# Power.net
KiCad netlist of a schematic drawn in Altium Designer
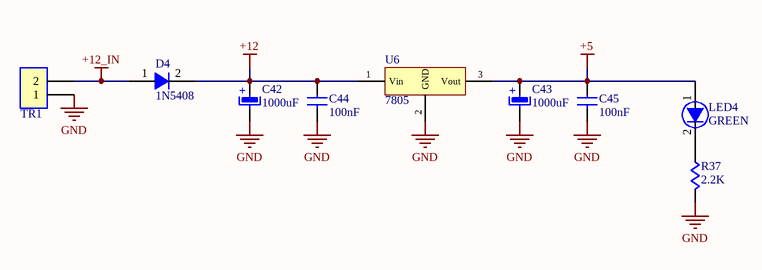
[diagram p0: Power.SchDoc]

(export (version "E")
  (design (tool "Eeschema 10.0.6"))
  (components
    (comp (ref "C42")
      (value "1000uF")
      (footprint "CAP-Elec-10x25-5")
      (description "CAPACITOR")
      (fields
        (field (name "VOLTAGE") "25V")
        (field (name "Comment") "CAP Elec 1000uF-25V-10x25-THD")
        (field (name "PUBLISHER") "Mahdi Bagherzadeh")
      )
      (libsource (lib "Mahdi-Bagherzadeh") (part "CAP-ELEC"))
    )
    (comp (ref "C43")
      (value "1000uF")
      (footprint "CAP-ELEC-SMD-D")
      (description "CAPACITOR")
      (fields
        (field (name "VOLTAGE") "10V")
        (field (name "Comment") "CAP Elec 1000uF-10V-10x25-THD")
        (field (name "PUBLISHER") "Mahdi Bagherzadeh")
      )
      (libsource (lib "Mahdi-Bagherzadeh") (part "CAP-ELEC"))
    )
    (comp (ref "C44")
      (value "100nF")
      (footprint "C-0805")
      (description "CAPACITOR")
      (fields
        (field (name "VOLTAGE") "50V")
        (field (name "TOLERANCE") "X7R")
        (field (name "PUBLISHER") "Mahdi Bagherzadeh")
      )
      (libsource (lib "Mahdi-Bagherzadeh") (part "CAP-CER"))
    )
    (comp (ref "C45")
      (value "100nF")
      (footprint "C-0805")
      (description "CAPACITOR")
      (fields
        (field (name "VOLTAGE") "50V")
        (field (name "TOLERANCE") "X7R")
        (field (name "PUBLISHER") "Mahdi Bagherzadeh")
      )
      (libsource (lib "Mahdi-Bagherzadeh") (part "CAP-CER"))
    )
    (comp (ref "D4")
      (value "Diode 1N5408-SMD")
      (footprint "D-DO214")
      (description "DIODE")
      (fields (field (name "CODE") "1N5408") (field (name "PUBLISHER") "Mahdi Bagherzadeh"))
      (libsource (lib "Mahdi-Bagherzadeh") (part "DIODE"))
    )
    (comp (ref "LED4")
      (value "LED GREEN-1206-SMD")
      (footprint "LED-1206-Y")
      (description "LED")
      (fields (field (name "COLOR") "GREEN") (field (name "PUBLISHER") "Mahdi Bagherzadeh"))
      (libsource (lib "Mahdi-Bagherzadeh") (part "LED"))
    )
    (comp (ref "R37")
      (value "2.2K")
      (footprint "RES-THD-1W-hori-Ls700mil")
      (description "RESISTOR")
      (fields
        (field (name "TOLERANCE") "5%")
        (field (name "POWER") "1/8W")
        (field (name "PUBLISHER") "Mahdi Bagherzadeh")
      )
      (libsource (lib "Mahdi-Bagherzadeh") (part "RES"))
    )
    (comp (ref "TR1")
      (value "Terminal KF?/Phoenix-2Pin-?mm-Straight/Right")
      (footprint "KF129-2pin")
      (description "TERMINAL")
      (fields (field (name "PUBLISHER") "Mahdi Bagherzadeh"))
      (libsource (lib "Mahdi-Bagherzadeh") (part "TEMINAL-2pin"))
    )
    (comp (ref "U6")
      (value "Reg 7805-5V-THD")
      (footprint "TO220-HEARSINK-1")
      (description "REGULATOR")
      (fields
        (field (name "VOLTAGE") "5V")
        (field (name "CODE") "7805")
        (field (name "PUBLISHER") "Mahdi Bagherzadeh")
      )
      (libsource (lib "Mahdi-Bagherzadeh") (part "78Mxx"))
    )
  )
  (nets
    (net (code "1") (name "+5") (class "Default")
      (node (ref "C43") (pin "1") (pinfunction "1_1") (pintype "passive"))
      (node (ref "C45") (pin "1") (pinfunction "1_1") (pintype "passive"))
      (node (ref "LED4") (pin "1") (pinfunction "A_1") (pintype "passive"))
      (node (ref "U6") (pin "3") (pinfunction "Vout_3") (pintype "power_in"))
    )
    (net (code "2") (name "+12") (class "Default")
      (node (ref "C42") (pin "1") (pinfunction "1_1") (pintype "passive"))
      (node (ref "C44") (pin "1") (pinfunction "1_1") (pintype "passive"))
      (node (ref "D4") (pin "2") (pinfunction "C_2") (pintype "passive"))
      (node (ref "U6") (pin "1") (pinfunction "Vin_1") (pintype "power_in"))
    )
    (net (code "3") (name "+12_IN") (class "Default")
      (node (ref "D4") (pin "1") (pinfunction "A_1") (pintype "passive"))
      (node (ref "TR1") (pin "2") (pinfunction "2_2") (pintype "passive"))
    )
    (net (code "4") (name "GND") (class "Default")
      (node (ref "C42") (pin "2") (pinfunction "2_2") (pintype "passive"))
      (node (ref "C43") (pin "2") (pinfunction "2_2") (pintype "passive"))
      (node (ref "C44") (pin "2") (pinfunction "2_2") (pintype "passive"))
      (node (ref "C45") (pin "2") (pinfunction "2_2") (pintype "passive"))
      (node (ref "R37") (pin "2") (pinfunction "2_2") (pintype "passive"))
      (node (ref "TR1") (pin "1") (pinfunction "1_1") (pintype "passive"))
      (node (ref "U6") (pin "2") (pinfunction "GND_2") (pintype "power_in"))
    )
    (net (code "5") (name "Net-(LED4-C)") (class "Default")
      (node (ref "LED4") (pin "2") (pinfunction "C_2") (pintype "passive"))
      (node (ref "R37") (pin "1") (pinfunction "1_1") (pintype "passive"))
    )
  )
)
